# Main_board.net
KiCad netlist of a schematic drawn in EAGLE
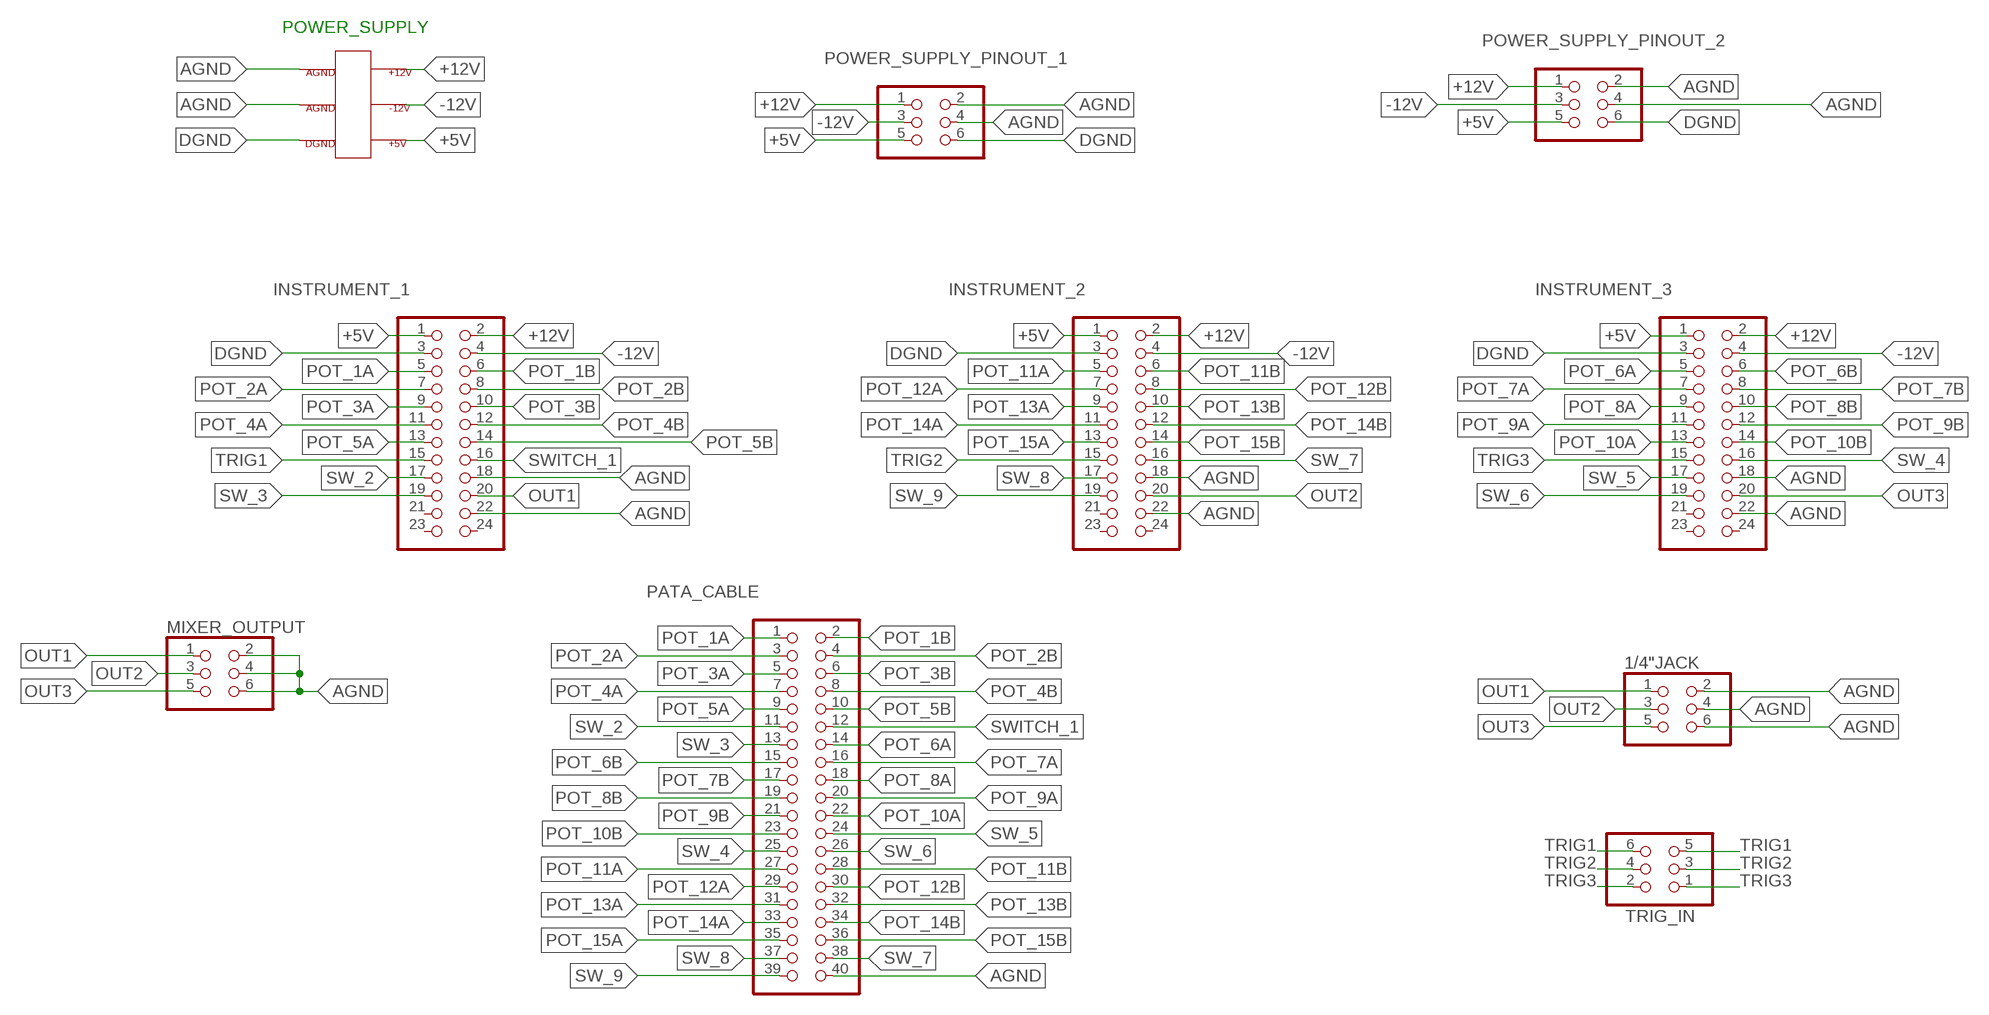
[diagram p0: schematic, sheet 1]

(export (version "E")
  (design (tool "Eeschema 10.0.6"))
  (components
    (comp (ref "1/4\"JACK")
      (value "PINHD-2X3")
      (footprint "eagle-import:2X03")
      (libsource (lib "eagle-import") (part "PINHD-2X3"))
    )
    (comp (ref "INSTRUMENT_1")
      (value "PINHD-2X12")
      (footprint "eagle-import:2X12")
      (libsource (lib "eagle-import") (part "PINHD-2X12"))
    )
    (comp (ref "INSTRUMENT_2")
      (value "PINHD-2X12")
      (footprint "eagle-import:2X12")
      (libsource (lib "eagle-import") (part "PINHD-2X12"))
    )
    (comp (ref "INSTRUMENT_3")
      (value "PINHD-2X12")
      (footprint "eagle-import:2X12")
      (libsource (lib "eagle-import") (part "PINHD-2X12"))
    )
    (comp (ref "MIXER_OUTPUT")
      (value "PINHD-2X3")
      (footprint "eagle-import:2X03")
      (libsource (lib "eagle-import") (part "PINHD-2X3"))
    )
    (comp (ref "PATA_CABLE")
      (value "PINHD-2X20")
      (footprint "eagle-import:2X20")
      (libsource (lib "eagle-import") (part "PINHD-2X20"))
    )
    (comp (ref "POWER_SUPPLY")
      (value "TER6PIN_VERT")
      (footprint "eagle-import:CAPSTONE_1-770875-0")
      (libsource (lib "eagle-import") (part "TER6PIN_VERT"))
    )
    (comp (ref "POWER_SUPPLY_PINOUT_1")
      (value "PINHD-2X3")
      (footprint "eagle-import:2X03")
      (libsource (lib "eagle-import") (part "PINHD-2X3"))
    )
    (comp (ref "POWER_SUPPLY_PINOUT_2")
      (value "PINHD-2X3")
      (footprint "eagle-import:2X03")
      (libsource (lib "eagle-import") (part "PINHD-2X3"))
    )
    (comp (ref "TRIG_IN")
      (value "PINHD-2X3")
      (footprint "eagle-import:2X03")
      (libsource (lib "eagle-import") (part "PINHD-2X3"))
    )
  )
  (nets
    (net (code "1") (name "+5V") (class "Default")
      (node (ref "INSTRUMENT_1") (pin "1") (pinfunction "1_1") (pintype "passive"))
      (node (ref "INSTRUMENT_2") (pin "1") (pinfunction "1_1") (pintype "passive"))
      (node (ref "INSTRUMENT_3") (pin "1") (pinfunction "1_1") (pintype "passive"))
      (node (ref "POWER_SUPPLY") (pin "+5V") (pinfunction "+5V_+5V") (pintype "bidirectional"))
      (node (ref "POWER_SUPPLY") (pin "NULL") (pinfunction "+5V_NULL") (pintype "bidirectional"))
      (node (ref "POWER_SUPPLY_PINOUT_1") (pin "5") (pinfunction "5_5") (pintype "passive"))
      (node (ref "POWER_SUPPLY_PINOUT_2") (pin "5") (pinfunction "5_5") (pintype "passive"))
    )
    (net (code "2") (name "+12V") (class "Default")
      (node (ref "INSTRUMENT_1") (pin "2") (pinfunction "2_2") (pintype "passive"))
      (node (ref "INSTRUMENT_2") (pin "2") (pinfunction "2_2") (pintype "passive"))
      (node (ref "INSTRUMENT_3") (pin "2") (pinfunction "2_2") (pintype "passive"))
      (node (ref "POWER_SUPPLY") (pin "+12V") (pinfunction "+12V_+12V") (pintype "bidirectional"))
      (node (ref "POWER_SUPPLY_PINOUT_1") (pin "1") (pinfunction "1_1") (pintype "passive"))
      (node (ref "POWER_SUPPLY_PINOUT_2") (pin "1") (pinfunction "1_1") (pintype "passive"))
    )
    (net (code "3") (name "-12V") (class "Default")
      (node (ref "INSTRUMENT_1") (pin "4") (pinfunction "4_4") (pintype "passive"))
      (node (ref "INSTRUMENT_2") (pin "4") (pinfunction "4_4") (pintype "passive"))
      (node (ref "INSTRUMENT_3") (pin "4") (pinfunction "4_4") (pintype "passive"))
      (node (ref "POWER_SUPPLY") (pin "-12V") (pinfunction "-12V_-12V") (pintype "bidirectional"))
      (node (ref "POWER_SUPPLY_PINOUT_1") (pin "3") (pinfunction "3_3") (pintype "passive"))
      (node (ref "POWER_SUPPLY_PINOUT_2") (pin "3") (pinfunction "3_3") (pintype "passive"))
    )
    (net (code "4") (name "AGND") (class "Default")
      (node (ref "1/4\"JACK") (pin "2") (pinfunction "2_2") (pintype "passive"))
      (node (ref "1/4\"JACK") (pin "4") (pinfunction "4_4") (pintype "passive"))
      (node (ref "1/4\"JACK") (pin "6") (pinfunction "6_6") (pintype "passive"))
      (node (ref "INSTRUMENT_1") (pin "18") (pinfunction "18_18") (pintype "passive"))
      (node (ref "INSTRUMENT_1") (pin "22") (pinfunction "22_22") (pintype "passive"))
      (node (ref "INSTRUMENT_2") (pin "18") (pinfunction "18_18") (pintype "passive"))
      (node (ref "INSTRUMENT_2") (pin "22") (pinfunction "22_22") (pintype "passive"))
      (node (ref "INSTRUMENT_3") (pin "18") (pinfunction "18_18") (pintype "passive"))
      (node (ref "INSTRUMENT_3") (pin "22") (pinfunction "22_22") (pintype "passive"))
      (node (ref "MIXER_OUTPUT") (pin "2") (pinfunction "2_2") (pintype "passive"))
      (node (ref "MIXER_OUTPUT") (pin "4") (pinfunction "4_4") (pintype "passive"))
      (node (ref "MIXER_OUTPUT") (pin "6") (pinfunction "6_6") (pintype "passive"))
      (node (ref "PATA_CABLE") (pin "40") (pinfunction "40_40") (pintype "passive"))
      (node (ref "POWER_SUPPLY") (pin "AGND0") (pinfunction "AGND0_AGND0") (pintype "bidirectional"))
      (node (ref "POWER_SUPPLY") (pin "AGND1") (pinfunction "AGND1_AGND1") (pintype "bidirectional"))
      (node (ref "POWER_SUPPLY_PINOUT_1") (pin "2") (pinfunction "2_2") (pintype "passive"))
      (node (ref "POWER_SUPPLY_PINOUT_1") (pin "4") (pinfunction "4_4") (pintype "passive"))
      (node (ref "POWER_SUPPLY_PINOUT_2") (pin "2") (pinfunction "2_2") (pintype "passive"))
      (node (ref "POWER_SUPPLY_PINOUT_2") (pin "4") (pinfunction "4_4") (pintype "passive"))
    )
    (net (code "5") (name "DGND") (class "Default")
      (node (ref "INSTRUMENT_1") (pin "3") (pinfunction "3_3") (pintype "passive"))
      (node (ref "INSTRUMENT_2") (pin "3") (pinfunction "3_3") (pintype "passive"))
      (node (ref "INSTRUMENT_3") (pin "3") (pinfunction "3_3") (pintype "passive"))
      (node (ref "POWER_SUPPLY") (pin "DGND") (pinfunction "DGND_DGND") (pintype "bidirectional"))
      (node (ref "POWER_SUPPLY_PINOUT_1") (pin "6") (pinfunction "6_6") (pintype "passive"))
      (node (ref "POWER_SUPPLY_PINOUT_2") (pin "6") (pinfunction "6_6") (pintype "passive"))
    )
    (net (code "6") (name "OUT1") (class "Default")
      (node (ref "1/4\"JACK") (pin "1") (pinfunction "1_1") (pintype "passive"))
      (node (ref "INSTRUMENT_1") (pin "20") (pinfunction "20_20") (pintype "passive"))
      (node (ref "MIXER_OUTPUT") (pin "1") (pinfunction "1_1") (pintype "passive"))
    )
    (net (code "7") (name "OUT2") (class "Default")
      (node (ref "1/4\"JACK") (pin "3") (pinfunction "3_3") (pintype "passive"))
      (node (ref "INSTRUMENT_2") (pin "20") (pinfunction "20_20") (pintype "passive"))
      (node (ref "MIXER_OUTPUT") (pin "3") (pinfunction "3_3") (pintype "passive"))
    )
    (net (code "8") (name "OUT3") (class "Default")
      (node (ref "1/4\"JACK") (pin "5") (pinfunction "5_5") (pintype "passive"))
      (node (ref "INSTRUMENT_3") (pin "20") (pinfunction "20_20") (pintype "passive"))
      (node (ref "MIXER_OUTPUT") (pin "5") (pinfunction "5_5") (pintype "passive"))
    )
    (net (code "9") (name "POT_1A") (class "Default")
      (node (ref "INSTRUMENT_1") (pin "5") (pinfunction "5_5") (pintype "passive"))
      (node (ref "PATA_CABLE") (pin "1") (pinfunction "1_1") (pintype "passive"))
    )
    (net (code "10") (name "POT_1B") (class "Default")
      (node (ref "INSTRUMENT_1") (pin "6") (pinfunction "6_6") (pintype "passive"))
      (node (ref "PATA_CABLE") (pin "2") (pinfunction "2_2") (pintype "passive"))
    )
    (net (code "11") (name "POT_2A") (class "Default")
      (node (ref "INSTRUMENT_1") (pin "7") (pinfunction "7_7") (pintype "passive"))
      (node (ref "PATA_CABLE") (pin "3") (pinfunction "3_3") (pintype "passive"))
    )
    (net (code "12") (name "POT_2B") (class "Default")
      (node (ref "INSTRUMENT_1") (pin "8") (pinfunction "8_8") (pintype "passive"))
      (node (ref "PATA_CABLE") (pin "4") (pinfunction "4_4") (pintype "passive"))
    )
    (net (code "13") (name "POT_3A") (class "Default")
      (node (ref "INSTRUMENT_1") (pin "9") (pinfunction "9_9") (pintype "passive"))
      (node (ref "PATA_CABLE") (pin "5") (pinfunction "5_5") (pintype "passive"))
    )
    (net (code "14") (name "POT_3B") (class "Default")
      (node (ref "INSTRUMENT_1") (pin "10") (pinfunction "10_10") (pintype "passive"))
      (node (ref "PATA_CABLE") (pin "6") (pinfunction "6_6") (pintype "passive"))
    )
    (net (code "15") (name "POT_4A") (class "Default")
      (node (ref "INSTRUMENT_1") (pin "11") (pinfunction "11_11") (pintype "passive"))
      (node (ref "PATA_CABLE") (pin "7") (pinfunction "7_7") (pintype "passive"))
    )
    (net (code "16") (name "POT_4B") (class "Default")
      (node (ref "INSTRUMENT_1") (pin "12") (pinfunction "12_12") (pintype "passive"))
      (node (ref "PATA_CABLE") (pin "8") (pinfunction "8_8") (pintype "passive"))
    )
    (net (code "17") (name "POT_5A") (class "Default")
      (node (ref "INSTRUMENT_1") (pin "13") (pinfunction "13_13") (pintype "passive"))
      (node (ref "PATA_CABLE") (pin "9") (pinfunction "9_9") (pintype "passive"))
    )
    (net (code "18") (name "POT_5B") (class "Default")
      (node (ref "INSTRUMENT_1") (pin "14") (pinfunction "14_14") (pintype "passive"))
      (node (ref "PATA_CABLE") (pin "10") (pinfunction "10_10") (pintype "passive"))
    )
    (net (code "19") (name "POT_6A") (class "Default")
      (node (ref "INSTRUMENT_3") (pin "5") (pinfunction "5_5") (pintype "passive"))
      (node (ref "PATA_CABLE") (pin "14") (pinfunction "14_14") (pintype "passive"))
    )
    (net (code "20") (name "POT_6B") (class "Default")
      (node (ref "INSTRUMENT_3") (pin "6") (pinfunction "6_6") (pintype "passive"))
      (node (ref "PATA_CABLE") (pin "15") (pinfunction "15_15") (pintype "passive"))
    )
    (net (code "21") (name "POT_7A") (class "Default")
      (node (ref "INSTRUMENT_3") (pin "7") (pinfunction "7_7") (pintype "passive"))
      (node (ref "PATA_CABLE") (pin "16") (pinfunction "16_16") (pintype "passive"))
    )
    (net (code "22") (name "POT_7B") (class "Default")
      (node (ref "INSTRUMENT_3") (pin "8") (pinfunction "8_8") (pintype "passive"))
      (node (ref "PATA_CABLE") (pin "17") (pinfunction "17_17") (pintype "passive"))
    )
    (net (code "23") (name "POT_8A") (class "Default")
      (node (ref "INSTRUMENT_3") (pin "9") (pinfunction "9_9") (pintype "passive"))
      (node (ref "PATA_CABLE") (pin "18") (pinfunction "18_18") (pintype "passive"))
    )
    (net (code "24") (name "POT_8B") (class "Default")
      (node (ref "INSTRUMENT_3") (pin "10") (pinfunction "10_10") (pintype "passive"))
      (node (ref "PATA_CABLE") (pin "19") (pinfunction "19_19") (pintype "passive"))
    )
    (net (code "25") (name "POT_9A") (class "Default")
      (node (ref "INSTRUMENT_3") (pin "11") (pinfunction "11_11") (pintype "passive"))
      (node (ref "PATA_CABLE") (pin "20") (pinfunction "20_20") (pintype "passive"))
    )
    (net (code "26") (name "POT_9B") (class "Default")
      (node (ref "INSTRUMENT_3") (pin "12") (pinfunction "12_12") (pintype "passive"))
      (node (ref "PATA_CABLE") (pin "21") (pinfunction "21_21") (pintype "passive"))
    )
    (net (code "27") (name "POT_10A") (class "Default")
      (node (ref "INSTRUMENT_3") (pin "13") (pinfunction "13_13") (pintype "passive"))
      (node (ref "PATA_CABLE") (pin "22") (pinfunction "22_22") (pintype "passive"))
    )
    (net (code "28") (name "POT_10B") (class "Default")
      (node (ref "INSTRUMENT_3") (pin "14") (pinfunction "14_14") (pintype "passive"))
      (node (ref "PATA_CABLE") (pin "23") (pinfunction "23_23") (pintype "passive"))
    )
    (net (code "29") (name "POT_11A") (class "Default")
      (node (ref "INSTRUMENT_2") (pin "5") (pinfunction "5_5") (pintype "passive"))
      (node (ref "PATA_CABLE") (pin "27") (pinfunction "27_27") (pintype "passive"))
    )
    (net (code "30") (name "POT_11B") (class "Default")
      (node (ref "INSTRUMENT_2") (pin "6") (pinfunction "6_6") (pintype "passive"))
      (node (ref "PATA_CABLE") (pin "28") (pinfunction "28_28") (pintype "passive"))
    )
    (net (code "31") (name "POT_12A") (class "Default")
      (node (ref "INSTRUMENT_2") (pin "7") (pinfunction "7_7") (pintype "passive"))
      (node (ref "PATA_CABLE") (pin "29") (pinfunction "29_29") (pintype "passive"))
    )
    (net (code "32") (name "POT_12B") (class "Default")
      (node (ref "INSTRUMENT_2") (pin "8") (pinfunction "8_8") (pintype "passive"))
      (node (ref "PATA_CABLE") (pin "30") (pinfunction "30_30") (pintype "passive"))
    )
    (net (code "33") (name "POT_13A") (class "Default")
      (node (ref "INSTRUMENT_2") (pin "9") (pinfunction "9_9") (pintype "passive"))
      (node (ref "PATA_CABLE") (pin "31") (pinfunction "31_31") (pintype "passive"))
    )
    (net (code "34") (name "POT_13B") (class "Default")
      (node (ref "INSTRUMENT_2") (pin "10") (pinfunction "10_10") (pintype "passive"))
      (node (ref "PATA_CABLE") (pin "32") (pinfunction "32_32") (pintype "passive"))
    )
    (net (code "35") (name "POT_14A") (class "Default")
      (node (ref "INSTRUMENT_2") (pin "11") (pinfunction "11_11") (pintype "passive"))
      (node (ref "PATA_CABLE") (pin "33") (pinfunction "33_33") (pintype "passive"))
    )
    (net (code "36") (name "POT_14B") (class "Default")
      (node (ref "INSTRUMENT_2") (pin "12") (pinfunction "12_12") (pintype "passive"))
      (node (ref "PATA_CABLE") (pin "34") (pinfunction "34_34") (pintype "passive"))
    )
    (net (code "37") (name "POT_15A") (class "Default")
      (node (ref "INSTRUMENT_2") (pin "13") (pinfunction "13_13") (pintype "passive"))
      (node (ref "PATA_CABLE") (pin "35") (pinfunction "35_35") (pintype "passive"))
    )
    (net (code "38") (name "POT_15B") (class "Default")
      (node (ref "INSTRUMENT_2") (pin "14") (pinfunction "14_14") (pintype "passive"))
      (node (ref "PATA_CABLE") (pin "36") (pinfunction "36_36") (pintype "passive"))
    )
    (net (code "39") (name "SWITCH_1") (class "Default")
      (node (ref "INSTRUMENT_1") (pin "16") (pinfunction "16_16") (pintype "passive"))
      (node (ref "PATA_CABLE") (pin "12") (pinfunction "12_12") (pintype "passive"))
    )
    (net (code "40") (name "SW_2") (class "Default")
      (node (ref "INSTRUMENT_1") (pin "17") (pinfunction "17_17") (pintype "passive"))
      (node (ref "PATA_CABLE") (pin "11") (pinfunction "11_11") (pintype "passive"))
    )
    (net (code "41") (name "SW_3") (class "Default")
      (node (ref "INSTRUMENT_1") (pin "19") (pinfunction "19_19") (pintype "passive"))
      (node (ref "PATA_CABLE") (pin "13") (pinfunction "13_13") (pintype "passive"))
    )
    (net (code "42") (name "SW_4") (class "Default")
      (node (ref "INSTRUMENT_3") (pin "16") (pinfunction "16_16") (pintype "passive"))
      (node (ref "PATA_CABLE") (pin "25") (pinfunction "25_25") (pintype "passive"))
    )
    (net (code "43") (name "SW_5") (class "Default")
      (node (ref "INSTRUMENT_3") (pin "17") (pinfunction "17_17") (pintype "passive"))
      (node (ref "PATA_CABLE") (pin "24") (pinfunction "24_24") (pintype "passive"))
    )
    (net (code "44") (name "SW_6") (class "Default")
      (node (ref "INSTRUMENT_3") (pin "19") (pinfunction "19_19") (pintype "passive"))
      (node (ref "PATA_CABLE") (pin "26") (pinfunction "26_26") (pintype "passive"))
    )
    (net (code "45") (name "SW_7") (class "Default")
      (node (ref "INSTRUMENT_2") (pin "16") (pinfunction "16_16") (pintype "passive"))
      (node (ref "PATA_CABLE") (pin "38") (pinfunction "38_38") (pintype "passive"))
    )
    (net (code "46") (name "SW_8") (class "Default")
      (node (ref "INSTRUMENT_2") (pin "17") (pinfunction "17_17") (pintype "passive"))
      (node (ref "PATA_CABLE") (pin "37") (pinfunction "37_37") (pintype "passive"))
    )
    (net (code "47") (name "SW_9") (class "Default")
      (node (ref "INSTRUMENT_2") (pin "19") (pinfunction "19_19") (pintype "passive"))
      (node (ref "PATA_CABLE") (pin "39") (pinfunction "39_39") (pintype "passive"))
    )
    (net (code "48") (name "TRIG1") (class "Default")
      (node (ref "INSTRUMENT_1") (pin "15") (pinfunction "15_15") (pintype "passive"))
      (node (ref "TRIG_IN") (pin "5") (pinfunction "5_5") (pintype "passive"))
      (node (ref "TRIG_IN") (pin "6") (pinfunction "6_6") (pintype "passive"))
    )
    (net (code "49") (name "TRIG2") (class "Default")
      (node (ref "INSTRUMENT_2") (pin "15") (pinfunction "15_15") (pintype "passive"))
      (node (ref "TRIG_IN") (pin "3") (pinfunction "3_3") (pintype "passive"))
      (node (ref "TRIG_IN") (pin "4") (pinfunction "4_4") (pintype "passive"))
    )
    (net (code "50") (name "TRIG3") (class "Default")
      (node (ref "INSTRUMENT_3") (pin "15") (pinfunction "15_15") (pintype "passive"))
      (node (ref "TRIG_IN") (pin "1") (pinfunction "1_1") (pintype "passive"))
      (node (ref "TRIG_IN") (pin "2") (pinfunction "2_2") (pintype "passive"))
    )
    (net (code "51") (name "unconnected-(INSTRUMENT_1-Pad21)") (class "Default")
      (node (ref "INSTRUMENT_1") (pin "21") (pinfunction "21_21") (pintype "passive"))
    )
    (net (code "52") (name "unconnected-(INSTRUMENT_1-Pad23)") (class "Default")
      (node (ref "INSTRUMENT_1") (pin "23") (pinfunction "23_23") (pintype "passive"))
    )
    (net (code "53") (name "unconnected-(INSTRUMENT_1-Pad24)") (class "Default")
      (node (ref "INSTRUMENT_1") (pin "24") (pinfunction "24_24") (pintype "passive"))
    )
    (net (code "54") (name "unconnected-(INSTRUMENT_2-Pad21)") (class "Default")
      (node (ref "INSTRUMENT_2") (pin "21") (pinfunction "21_21") (pintype "passive"))
    )
    (net (code "55") (name "unconnected-(INSTRUMENT_2-Pad23)") (class "Default")
      (node (ref "INSTRUMENT_2") (pin "23") (pinfunction "23_23") (pintype "passive"))
    )
    (net (code "56") (name "unconnected-(INSTRUMENT_2-Pad24)") (class "Default")
      (node (ref "INSTRUMENT_2") (pin "24") (pinfunction "24_24") (pintype "passive"))
    )
    (net (code "57") (name "unconnected-(INSTRUMENT_3-Pad21)") (class "Default")
      (node (ref "INSTRUMENT_3") (pin "21") (pinfunction "21_21") (pintype "passive"))
    )
    (net (code "58") (name "unconnected-(INSTRUMENT_3-Pad23)") (class "Default")
      (node (ref "INSTRUMENT_3") (pin "23") (pinfunction "23_23") (pintype "passive"))
    )
    (net (code "59") (name "unconnected-(INSTRUMENT_3-Pad24)") (class "Default")
      (node (ref "INSTRUMENT_3") (pin "24") (pinfunction "24_24") (pintype "passive"))
    )
  )
)
